# cable.net
KiCad netlist of a schematic drawn in EAGLE
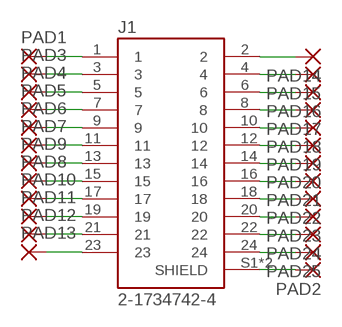
[diagram p0: schematic, sheet 1]

(export (version "E")
  (design (tool "Eeschema 10.0.6"))
  (components
    (comp (ref "J1")
      (value "2-1734742-4")
      (footprint "eagle-import:TE_2-1734742-4")
      (fields (field (name "MF") "TE Connectivity"))
      (libsource (lib "eagle-import") (part "2-1734742-4"))
    )
    (comp (ref "PAD1")
      (value "SMD2")
      (footprint "eagle-import:SMD1,27-2,54")
      (libsource (lib "eagle-import") (part "SMD2"))
    )
    (comp (ref "PAD2")
      (value "SMD2")
      (footprint "eagle-import:SMD1,27-2,54")
      (libsource (lib "eagle-import") (part "SMD2"))
    )
    (comp (ref "PAD3")
      (value "SMD2")
      (footprint "eagle-import:SMD1,27-2,54")
      (libsource (lib "eagle-import") (part "SMD2"))
    )
    (comp (ref "PAD4")
      (value "SMD2")
      (footprint "eagle-import:SMD1,27-2,54")
      (libsource (lib "eagle-import") (part "SMD2"))
    )
    (comp (ref "PAD5")
      (value "SMD2")
      (footprint "eagle-import:SMD1,27-2,54")
      (libsource (lib "eagle-import") (part "SMD2"))
    )
    (comp (ref "PAD6")
      (value "SMD2")
      (footprint "eagle-import:SMD1,27-2,54")
      (libsource (lib "eagle-import") (part "SMD2"))
    )
    (comp (ref "PAD7")
      (value "SMD2")
      (footprint "eagle-import:SMD1,27-2,54")
      (libsource (lib "eagle-import") (part "SMD2"))
    )
    (comp (ref "PAD8")
      (value "SMD2")
      (footprint "eagle-import:SMD1,27-2,54")
      (libsource (lib "eagle-import") (part "SMD2"))
    )
    (comp (ref "PAD9")
      (value "SMD2")
      (footprint "eagle-import:SMD1,27-2,54")
      (libsource (lib "eagle-import") (part "SMD2"))
    )
    (comp (ref "PAD10")
      (value "SMD2")
      (footprint "eagle-import:SMD1,27-2,54")
      (libsource (lib "eagle-import") (part "SMD2"))
    )
    (comp (ref "PAD11")
      (value "SMD2")
      (footprint "eagle-import:SMD1,27-2,54")
      (libsource (lib "eagle-import") (part "SMD2"))
    )
    (comp (ref "PAD12")
      (value "SMD2")
      (footprint "eagle-import:SMD1,27-2,54")
      (libsource (lib "eagle-import") (part "SMD2"))
    )
    (comp (ref "PAD13")
      (value "SMD2")
      (footprint "eagle-import:SMD1,27-2,54")
      (libsource (lib "eagle-import") (part "SMD2"))
    )
    (comp (ref "PAD14")
      (value "SMD2")
      (footprint "eagle-import:SMD1,27-2,54")
      (libsource (lib "eagle-import") (part "SMD2"))
    )
    (comp (ref "PAD15")
      (value "SMD2")
      (footprint "eagle-import:SMD1,27-2,54")
      (libsource (lib "eagle-import") (part "SMD2"))
    )
    (comp (ref "PAD16")
      (value "SMD2")
      (footprint "eagle-import:SMD1,27-2,54")
      (libsource (lib "eagle-import") (part "SMD2"))
    )
    (comp (ref "PAD17")
      (value "SMD2")
      (footprint "eagle-import:SMD1,27-2,54")
      (libsource (lib "eagle-import") (part "SMD2"))
    )
    (comp (ref "PAD18")
      (value "SMD2")
      (footprint "eagle-import:SMD1,27-2,54")
      (libsource (lib "eagle-import") (part "SMD2"))
    )
    (comp (ref "PAD19")
      (value "SMD2")
      (footprint "eagle-import:SMD1,27-2,54")
      (libsource (lib "eagle-import") (part "SMD2"))
    )
    (comp (ref "PAD20")
      (value "SMD2")
      (footprint "eagle-import:SMD1,27-2,54")
      (libsource (lib "eagle-import") (part "SMD2"))
    )
    (comp (ref "PAD21")
      (value "SMD2")
      (footprint "eagle-import:SMD1,27-2,54")
      (libsource (lib "eagle-import") (part "SMD2"))
    )
    (comp (ref "PAD22")
      (value "SMD2")
      (footprint "eagle-import:SMD1,27-2,54")
      (libsource (lib "eagle-import") (part "SMD2"))
    )
    (comp (ref "PAD23")
      (value "SMD2")
      (footprint "eagle-import:SMD1,27-2,54")
      (libsource (lib "eagle-import") (part "SMD2"))
    )
    (comp (ref "PAD24")
      (value "SMD2")
      (footprint "eagle-import:SMD1,27-2,54")
      (libsource (lib "eagle-import") (part "SMD2"))
    )
    (comp (ref "PAD25")
      (value "SMD2")
      (footprint "eagle-import:SMD1,27-2,54")
      (libsource (lib "eagle-import") (part "SMD2"))
    )
  )
  (nets
    (net (code "1") (name "Net-(PAD1-P)") (class "Default")
      (node (ref "J1") (pin "1") (pinfunction "1_1") (pintype "passive"))
      (node (ref "PAD1") (pin "1") (pinfunction "P_1") (pintype "passive"))
    )
    (net (code "2") (name "Net-(PAD2-P)") (class "Default")
      (node (ref "J1") (pin "S1") (pinfunction "SHIELD_S1") (pintype "passive"))
      (node (ref "J1") (pin "S2") (pinfunction "SHIELD_S2") (pintype "passive"))
      (node (ref "PAD2") (pin "1") (pinfunction "P_1") (pintype "passive"))
    )
    (net (code "3") (name "Net-(PAD3-P)") (class "Default")
      (node (ref "J1") (pin "3") (pinfunction "3_3") (pintype "passive"))
      (node (ref "PAD3") (pin "1") (pinfunction "P_1") (pintype "passive"))
    )
    (net (code "4") (name "Net-(PAD4-P)") (class "Default")
      (node (ref "J1") (pin "5") (pinfunction "5_5") (pintype "passive"))
      (node (ref "PAD4") (pin "1") (pinfunction "P_1") (pintype "passive"))
    )
    (net (code "5") (name "Net-(PAD5-P)") (class "Default")
      (node (ref "J1") (pin "7") (pinfunction "7_7") (pintype "passive"))
      (node (ref "PAD5") (pin "1") (pinfunction "P_1") (pintype "passive"))
    )
    (net (code "6") (name "Net-(PAD6-P)") (class "Default")
      (node (ref "J1") (pin "9") (pinfunction "9_9") (pintype "passive"))
      (node (ref "PAD6") (pin "1") (pinfunction "P_1") (pintype "passive"))
    )
    (net (code "7") (name "Net-(PAD7-P)") (class "Default")
      (node (ref "J1") (pin "11") (pinfunction "11_11") (pintype "passive"))
      (node (ref "PAD7") (pin "1") (pinfunction "P_1") (pintype "passive"))
    )
    (net (code "8") (name "Net-(PAD8-P)") (class "Default")
      (node (ref "J1") (pin "15") (pinfunction "15_15") (pintype "passive"))
      (node (ref "PAD8") (pin "1") (pinfunction "P_1") (pintype "passive"))
    )
    (net (code "9") (name "Net-(PAD9-P)") (class "Default")
      (node (ref "J1") (pin "13") (pinfunction "13_13") (pintype "passive"))
      (node (ref "PAD9") (pin "1") (pinfunction "P_1") (pintype "passive"))
    )
    (net (code "10") (name "Net-(PAD10-P)") (class "Default")
      (node (ref "J1") (pin "17") (pinfunction "17_17") (pintype "passive"))
      (node (ref "PAD10") (pin "1") (pinfunction "P_1") (pintype "passive"))
    )
    (net (code "11") (name "Net-(PAD11-P)") (class "Default")
      (node (ref "J1") (pin "19") (pinfunction "19_19") (pintype "passive"))
      (node (ref "PAD11") (pin "1") (pinfunction "P_1") (pintype "passive"))
    )
    (net (code "12") (name "Net-(PAD12-P)") (class "Default")
      (node (ref "J1") (pin "21") (pinfunction "21_21") (pintype "passive"))
      (node (ref "PAD12") (pin "1") (pinfunction "P_1") (pintype "passive"))
    )
    (net (code "13") (name "Net-(PAD13-P)") (class "Default")
      (node (ref "J1") (pin "23") (pinfunction "23_23") (pintype "passive"))
      (node (ref "PAD13") (pin "1") (pinfunction "P_1") (pintype "passive"))
    )
    (net (code "14") (name "Net-(PAD14-P)") (class "Default")
      (node (ref "J1") (pin "2") (pinfunction "2_2") (pintype "passive"))
      (node (ref "PAD14") (pin "1") (pinfunction "P_1") (pintype "passive"))
    )
    (net (code "15") (name "Net-(PAD15-P)") (class "Default")
      (node (ref "J1") (pin "4") (pinfunction "4_4") (pintype "passive"))
      (node (ref "PAD15") (pin "1") (pinfunction "P_1") (pintype "passive"))
    )
    (net (code "16") (name "Net-(PAD16-P)") (class "Default")
      (node (ref "J1") (pin "6") (pinfunction "6_6") (pintype "passive"))
      (node (ref "PAD16") (pin "1") (pinfunction "P_1") (pintype "passive"))
    )
    (net (code "17") (name "Net-(PAD17-P)") (class "Default")
      (node (ref "J1") (pin "8") (pinfunction "8_8") (pintype "power_in"))
      (node (ref "PAD17") (pin "1") (pinfunction "P_1") (pintype "passive"))
    )
    (net (code "18") (name "Net-(PAD18-P)") (class "Default")
      (node (ref "J1") (pin "10") (pinfunction "10_10") (pintype "passive"))
      (node (ref "PAD18") (pin "1") (pinfunction "P_1") (pintype "passive"))
    )
    (net (code "19") (name "Net-(PAD19-P)") (class "Default")
      (node (ref "J1") (pin "12") (pinfunction "12_12") (pintype "passive"))
      (node (ref "PAD19") (pin "1") (pinfunction "P_1") (pintype "passive"))
    )
    (net (code "20") (name "Net-(PAD20-P)") (class "Default")
      (node (ref "J1") (pin "14") (pinfunction "14_14") (pintype "passive"))
      (node (ref "PAD20") (pin "1") (pinfunction "P_1") (pintype "passive"))
    )
    (net (code "21") (name "Net-(PAD21-P)") (class "Default")
      (node (ref "J1") (pin "16") (pinfunction "16_16") (pintype "passive"))
      (node (ref "PAD21") (pin "1") (pinfunction "P_1") (pintype "passive"))
    )
    (net (code "22") (name "Net-(PAD22-P)") (class "Default")
      (node (ref "J1") (pin "18") (pinfunction "18_18") (pintype "passive"))
      (node (ref "PAD22") (pin "1") (pinfunction "P_1") (pintype "passive"))
    )
    (net (code "23") (name "Net-(PAD23-P)") (class "Default")
      (node (ref "J1") (pin "20") (pinfunction "20_20") (pintype "passive"))
      (node (ref "PAD23") (pin "1") (pinfunction "P_1") (pintype "passive"))
    )
    (net (code "24") (name "Net-(PAD24-P)") (class "Default")
      (node (ref "J1") (pin "22") (pinfunction "22_22") (pintype "passive"))
      (node (ref "PAD24") (pin "1") (pinfunction "P_1") (pintype "passive"))
    )
    (net (code "25") (name "Net-(PAD25-P)") (class "Default")
      (node (ref "J1") (pin "24") (pinfunction "24_24") (pintype "passive"))
      (node (ref "PAD25") (pin "1") (pinfunction "P_1") (pintype "passive"))
    )
  )
)
